# M5_Atom.net
KiCad netlist of a schematic drawn in EAGLE
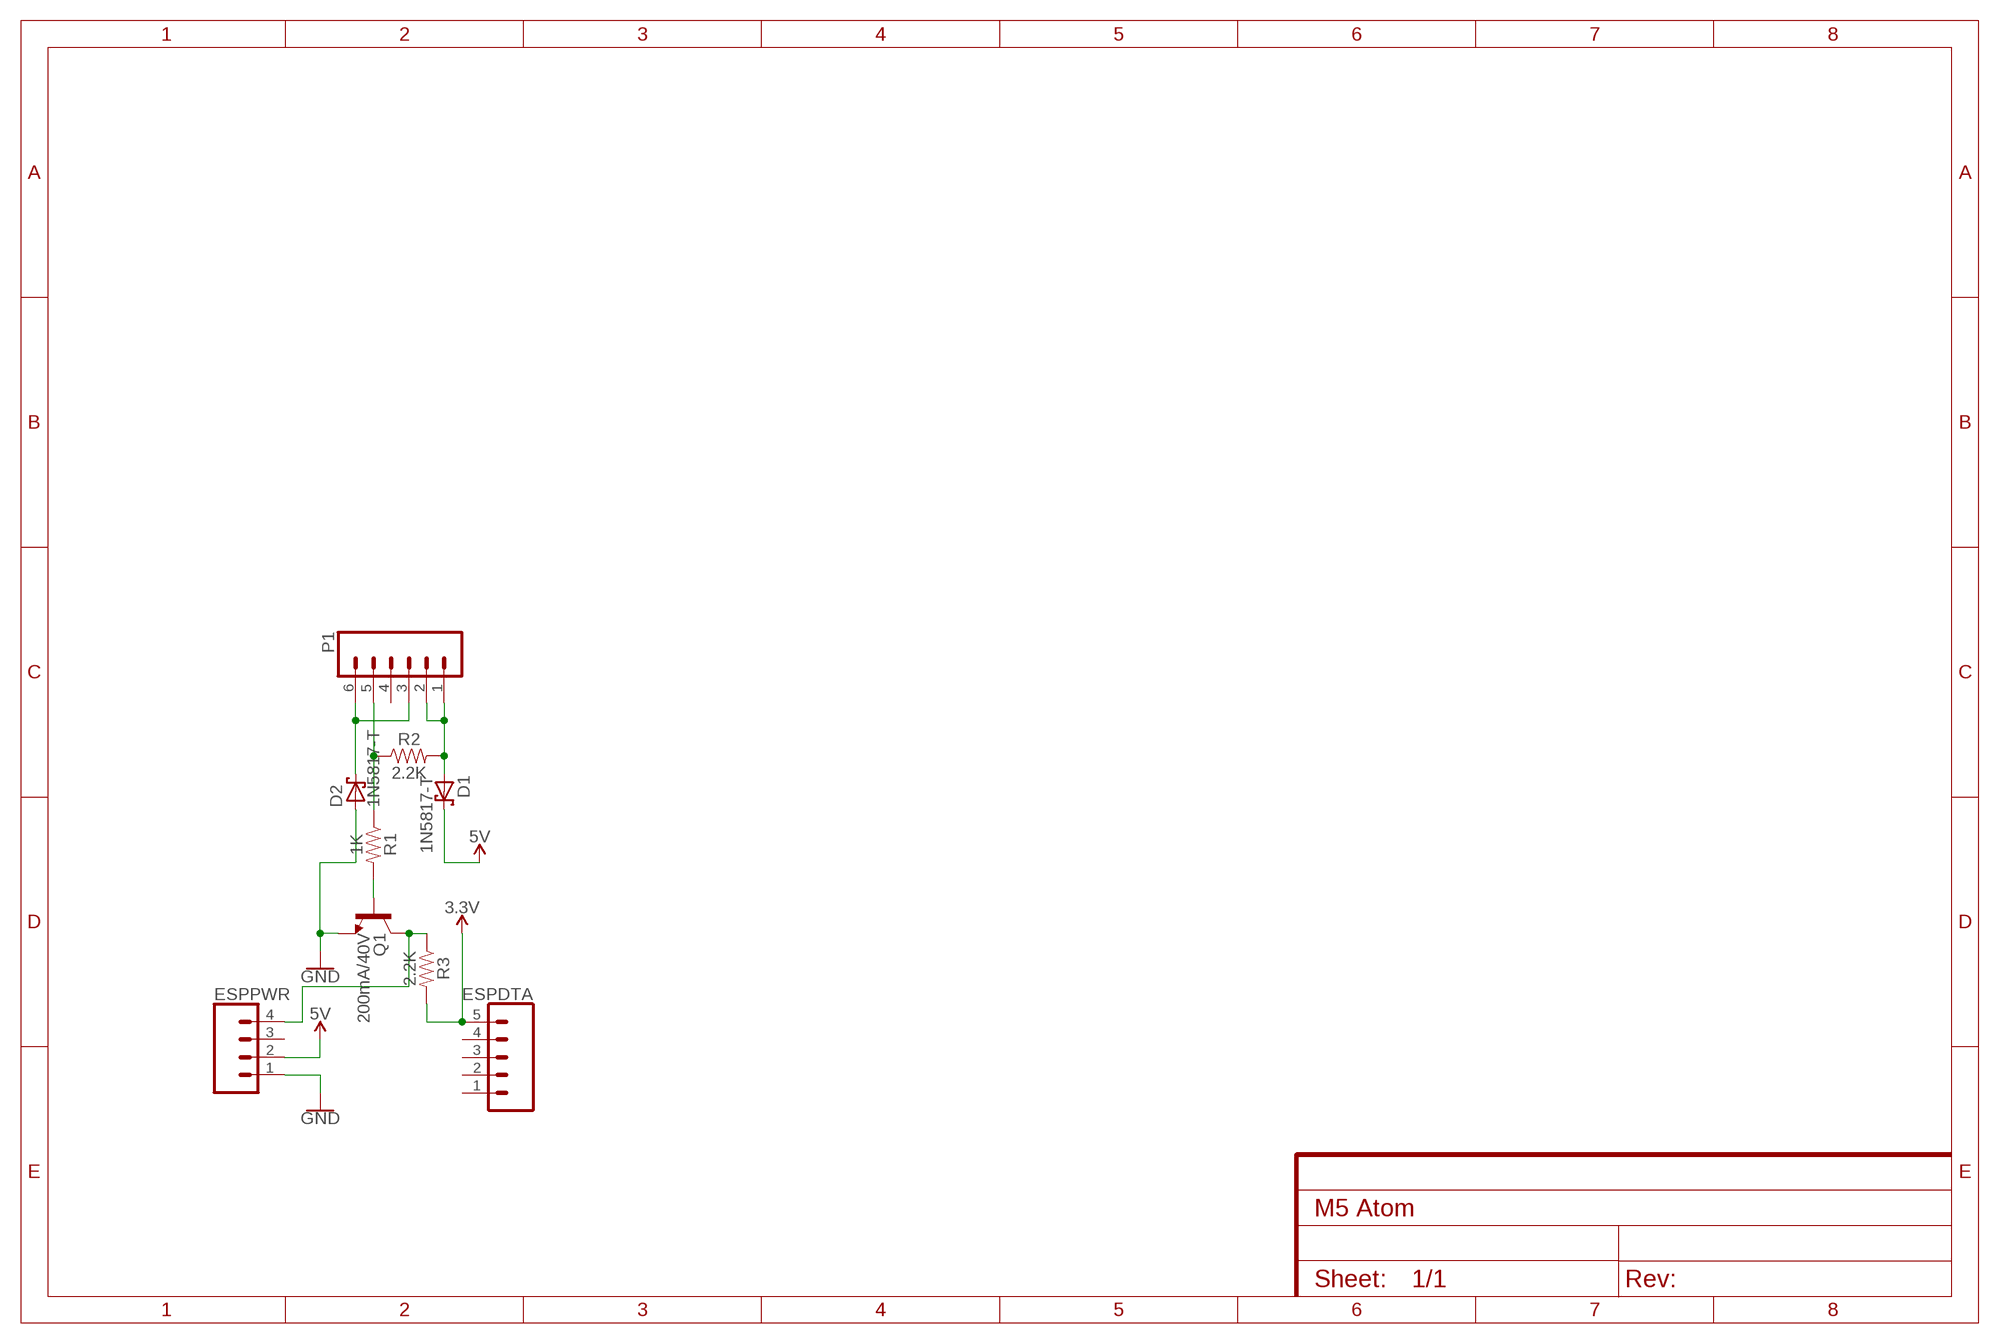
[diagram p0: schematic, sheet 1]

(export (version "E")
  (design (tool "Eeschema 10.0.6"))
  (components
    (comp (ref "D1")
      (value "1N5817-T")
      (footprint "eagle-import:DO41-7.6")
      (libsource (lib "eagle-import") (part "1N5817-T"))
    )
    (comp (ref "D2")
      (value "1N5817-T")
      (footprint "eagle-import:DO41-7.6")
      (libsource (lib "eagle-import") (part "1N5817-T"))
    )
    (comp (ref "ESPDTA")
      (value "CONN_05")
      (footprint "eagle-import:1X05")
      (libsource (lib "eagle-import") (part "CONN_05"))
    )
    (comp (ref "ESPPWR")
      (value "CONN_04PTH")
      (footprint "eagle-import:1X04")
      (libsource (lib "eagle-import") (part "CONN_04PTH"))
    )
    (comp (ref "P1")
      (value "CONN_06SILK_FEMALE_PTH")
      (footprint "eagle-import:1X06")
      (libsource (lib "eagle-import") (part "CONN_06SILK_FEMALE_PTH"))
    )
    (comp (ref "Q1")
      (value "200mA/40V")
      (footprint "eagle-import:TO-92")
      (libsource (lib "eagle-import") (part "TRANS_NPN-2N3904"))
    )
    (comp (ref "R1")
      (value "1K")
      (footprint "eagle-import:AXIAL-0.3")
      (libsource (lib "eagle-import") (part "RESISTORAXIAL-0.3"))
    )
    (comp (ref "R2")
      (value "2.2K")
      (footprint "eagle-import:AXIAL-0.3")
      (libsource (lib "eagle-import") (part "RESISTORAXIAL-0.3"))
    )
    (comp (ref "R3")
      (value "2.2K")
      (footprint "eagle-import:AXIAL-0.3")
      (libsource (lib "eagle-import") (part "RESISTORAXIAL-0.3"))
    )
  )
  (nets
    (net (code "1") (name "3.3V") (class "Default")
      (node (ref "ESPDTA") (pin "5") (pinfunction "5_5") (pintype "passive"))
      (node (ref "R3") (pin "P$2") (pinfunction "2_P$2") (pintype "passive"))
    )
    (net (code "2") (name "5V") (class "Default")
      (node (ref "D1") (pin "C") (pinfunction "C_C") (pintype "passive"))
      (node (ref "ESPPWR") (pin "2") (pinfunction "2_2") (pintype "passive"))
    )
    (net (code "3") (name "GND") (class "Default")
      (node (ref "D2") (pin "A") (pinfunction "A_A") (pintype "passive"))
      (node (ref "ESPPWR") (pin "1") (pinfunction "1_1") (pintype "passive"))
      (node (ref "Q1") (pin "1") (pinfunction "E_1") (pintype "passive"))
    )
    (net (code "4") (name "Net-(D2-PadC)") (class "Default")
      (node (ref "D2") (pin "C") (pinfunction "C_C") (pintype "passive"))
      (node (ref "P1") (pin "3") (pinfunction "3_3") (pintype "passive"))
      (node (ref "P1") (pin "6") (pinfunction "6_6") (pintype "passive"))
    )
    (net (code "5") (name "Net-(Q1-B)") (class "Default")
      (node (ref "Q1") (pin "2") (pinfunction "B_2") (pintype "passive"))
      (node (ref "R1") (pin "P$2") (pinfunction "2_P$2") (pintype "passive"))
    )
    (net (code "6") (name "Net-(Q1-C)") (class "Default")
      (node (ref "ESPPWR") (pin "4") (pinfunction "4_4") (pintype "passive"))
      (node (ref "Q1") (pin "3") (pinfunction "C_3") (pintype "passive"))
      (node (ref "R3") (pin "P$1") (pinfunction "1_P$1") (pintype "passive"))
    )
    (net (code "7") (name "Net-(R1-1)") (class "Default")
      (node (ref "P1") (pin "5") (pinfunction "5_5") (pintype "passive"))
      (node (ref "R1") (pin "P$1") (pinfunction "1_P$1") (pintype "passive"))
      (node (ref "R2") (pin "P$1") (pinfunction "1_P$1") (pintype "passive"))
    )
    (net (code "8") (name "Net-(R2-2)") (class "Default")
      (node (ref "D1") (pin "A") (pinfunction "A_A") (pintype "passive"))
      (node (ref "P1") (pin "1") (pinfunction "1_1") (pintype "passive"))
      (node (ref "P1") (pin "2") (pinfunction "2_2") (pintype "passive"))
      (node (ref "R2") (pin "P$2") (pinfunction "2_P$2") (pintype "passive"))
    )
    (net (code "9") (name "unconnected-(ESPDTA-Pad1)") (class "Default")
      (node (ref "ESPDTA") (pin "1") (pinfunction "1_1") (pintype "passive"))
    )
    (net (code "10") (name "unconnected-(ESPDTA-Pad2)") (class "Default")
      (node (ref "ESPDTA") (pin "2") (pinfunction "2_2") (pintype "passive"))
    )
    (net (code "11") (name "unconnected-(ESPDTA-Pad3)") (class "Default")
      (node (ref "ESPDTA") (pin "3") (pinfunction "3_3") (pintype "passive"))
    )
    (net (code "12") (name "unconnected-(ESPDTA-Pad4)") (class "Default")
      (node (ref "ESPDTA") (pin "4") (pinfunction "4_4") (pintype "passive"))
    )
    (net (code "13") (name "unconnected-(ESPPWR-Pad3)") (class "Default")
      (node (ref "ESPPWR") (pin "3") (pinfunction "3_3") (pintype "passive"))
    )
    (net (code "14") (name "unconnected-(P1-Pad4)") (class "Default")
      (node (ref "P1") (pin "4") (pinfunction "4_4") (pintype "passive"))
    )
  )
)
